# RaspberryPi-breakout-Alt.net
KiCad netlist of a schematic drawn in EAGLE
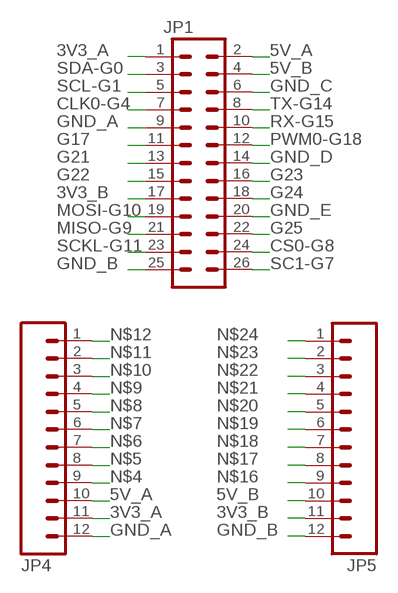
[diagram p0: schematic, sheet 1]

(export (version "E")
  (design (tool "Eeschema 10.0.6"))
  (components
    (comp (ref "JP1")
      (value "M13X22X13")
      (footprint "eagle-import:2X13")
      (libsource (lib "eagle-import") (part "M13X22X13"))
    )
    (comp (ref "JP4")
      (value "M12PTH")
      (footprint "eagle-import:1X12")
      (libsource (lib "eagle-import") (part "M12PTH"))
    )
    (comp (ref "JP5")
      (value "M12PTH")
      (footprint "eagle-import:1X12")
      (libsource (lib "eagle-import") (part "M12PTH"))
    )
  )
  (nets
    (net (code "1") (name "/3V3_A") (class "Default")
      (node (ref "JP1") (pin "1") (pinfunction "1_1") (pintype "passive"))
      (node (ref "JP4") (pin "11") (pinfunction "11_11") (pintype "passive"))
    )
    (net (code "2") (name "/3V3_B") (class "Default")
      (node (ref "JP1") (pin "17") (pinfunction "17_17") (pintype "passive"))
      (node (ref "JP5") (pin "11") (pinfunction "11_11") (pintype "passive"))
    )
    (net (code "3") (name "/5V_A") (class "Default")
      (node (ref "JP1") (pin "2") (pinfunction "2_2") (pintype "passive"))
      (node (ref "JP4") (pin "10") (pinfunction "10_10") (pintype "passive"))
    )
    (net (code "4") (name "/5V_B") (class "Default")
      (node (ref "JP1") (pin "4") (pinfunction "4_4") (pintype "passive"))
      (node (ref "JP5") (pin "10") (pinfunction "10_10") (pintype "passive"))
    )
    (net (code "5") (name "/CLK0-G4") (class "Default")
      (node (ref "JP1") (pin "7") (pinfunction "7_7") (pintype "passive"))
    )
    (net (code "6") (name "/CS0-G8") (class "Default")
      (node (ref "JP1") (pin "24") (pinfunction "24_24") (pintype "passive"))
    )
    (net (code "7") (name "/G17") (class "Default")
      (node (ref "JP1") (pin "11") (pinfunction "11_11") (pintype "passive"))
    )
    (net (code "8") (name "/G21") (class "Default")
      (node (ref "JP1") (pin "13") (pinfunction "13_13") (pintype "passive"))
    )
    (net (code "9") (name "/G22") (class "Default")
      (node (ref "JP1") (pin "15") (pinfunction "15_15") (pintype "passive"))
    )
    (net (code "10") (name "/G23") (class "Default")
      (node (ref "JP1") (pin "16") (pinfunction "16_16") (pintype "passive"))
    )
    (net (code "11") (name "/G24") (class "Default")
      (node (ref "JP1") (pin "18") (pinfunction "18_18") (pintype "passive"))
    )
    (net (code "12") (name "/G25") (class "Default")
      (node (ref "JP1") (pin "22") (pinfunction "22_22") (pintype "passive"))
    )
    (net (code "13") (name "/GND_A") (class "Default")
      (node (ref "JP1") (pin "9") (pinfunction "9_9") (pintype "passive"))
      (node (ref "JP4") (pin "12") (pinfunction "12_12") (pintype "passive"))
    )
    (net (code "14") (name "/GND_B") (class "Default")
      (node (ref "JP1") (pin "25") (pinfunction "25_25") (pintype "passive"))
      (node (ref "JP5") (pin "12") (pinfunction "12_12") (pintype "passive"))
    )
    (net (code "15") (name "/GND_C") (class "Default")
      (node (ref "JP1") (pin "6") (pinfunction "6_6") (pintype "passive"))
    )
    (net (code "16") (name "/GND_D") (class "Default")
      (node (ref "JP1") (pin "14") (pinfunction "14_14") (pintype "passive"))
    )
    (net (code "17") (name "/GND_E") (class "Default")
      (node (ref "JP1") (pin "20") (pinfunction "20_20") (pintype "passive"))
    )
    (net (code "18") (name "/MISO-G9") (class "Default")
      (node (ref "JP1") (pin "21") (pinfunction "21_21") (pintype "passive"))
    )
    (net (code "19") (name "/MOSI-G10") (class "Default")
      (node (ref "JP1") (pin "19") (pinfunction "19_19") (pintype "passive"))
    )
    (net (code "20") (name "/N$4") (class "Default")
      (node (ref "JP4") (pin "9") (pinfunction "9_9") (pintype "passive"))
    )
    (net (code "21") (name "/N$5") (class "Default")
      (node (ref "JP4") (pin "8") (pinfunction "8_8") (pintype "passive"))
    )
    (net (code "22") (name "/N$6") (class "Default")
      (node (ref "JP4") (pin "7") (pinfunction "7_7") (pintype "passive"))
    )
    (net (code "23") (name "/N$7") (class "Default")
      (node (ref "JP4") (pin "6") (pinfunction "6_6") (pintype "passive"))
    )
    (net (code "24") (name "/N$8") (class "Default")
      (node (ref "JP4") (pin "5") (pinfunction "5_5") (pintype "passive"))
    )
    (net (code "25") (name "/N$9") (class "Default")
      (node (ref "JP4") (pin "4") (pinfunction "4_4") (pintype "passive"))
    )
    (net (code "26") (name "/N$10") (class "Default")
      (node (ref "JP4") (pin "3") (pinfunction "3_3") (pintype "passive"))
    )
    (net (code "27") (name "/N$11") (class "Default")
      (node (ref "JP4") (pin "2") (pinfunction "2_2") (pintype "passive"))
    )
    (net (code "28") (name "/N$12") (class "Default")
      (node (ref "JP4") (pin "1") (pinfunction "1_1") (pintype "passive"))
    )
    (net (code "29") (name "/N$16") (class "Default")
      (node (ref "JP5") (pin "9") (pinfunction "9_9") (pintype "passive"))
    )
    (net (code "30") (name "/N$17") (class "Default")
      (node (ref "JP5") (pin "8") (pinfunction "8_8") (pintype "passive"))
    )
    (net (code "31") (name "/N$18") (class "Default")
      (node (ref "JP5") (pin "7") (pinfunction "7_7") (pintype "passive"))
    )
    (net (code "32") (name "/N$19") (class "Default")
      (node (ref "JP5") (pin "6") (pinfunction "6_6") (pintype "passive"))
    )
    (net (code "33") (name "/N$20") (class "Default")
      (node (ref "JP5") (pin "5") (pinfunction "5_5") (pintype "passive"))
    )
    (net (code "34") (name "/N$21") (class "Default")
      (node (ref "JP5") (pin "4") (pinfunction "4_4") (pintype "passive"))
    )
    (net (code "35") (name "/N$22") (class "Default")
      (node (ref "JP5") (pin "3") (pinfunction "3_3") (pintype "passive"))
    )
    (net (code "36") (name "/N$23") (class "Default")
      (node (ref "JP5") (pin "2") (pinfunction "2_2") (pintype "passive"))
    )
    (net (code "37") (name "/N$24") (class "Default")
      (node (ref "JP5") (pin "1") (pinfunction "1_1") (pintype "passive"))
    )
    (net (code "38") (name "/PWM0-G18") (class "Default")
      (node (ref "JP1") (pin "12") (pinfunction "12_12") (pintype "passive"))
    )
    (net (code "39") (name "/RX-G15") (class "Default")
      (node (ref "JP1") (pin "10") (pinfunction "10_10") (pintype "passive"))
    )
    (net (code "40") (name "/SC1-G7") (class "Default")
      (node (ref "JP1") (pin "26") (pinfunction "26_26") (pintype "passive"))
    )
    (net (code "41") (name "/SCKL-G11") (class "Default")
      (node (ref "JP1") (pin "23") (pinfunction "23_23") (pintype "passive"))
    )
    (net (code "42") (name "/SCL-G1") (class "Default")
      (node (ref "JP1") (pin "5") (pinfunction "5_5") (pintype "passive"))
    )
    (net (code "43") (name "/SDA-G0") (class "Default")
      (node (ref "JP1") (pin "3") (pinfunction "3_3") (pintype "passive"))
    )
    (net (code "44") (name "/TX-G14") (class "Default")
      (node (ref "JP1") (pin "8") (pinfunction "8_8") (pintype "passive"))
    )
  )
)
